# Round_Paws.net
KiCad netlist of a schematic drawn in EAGLE
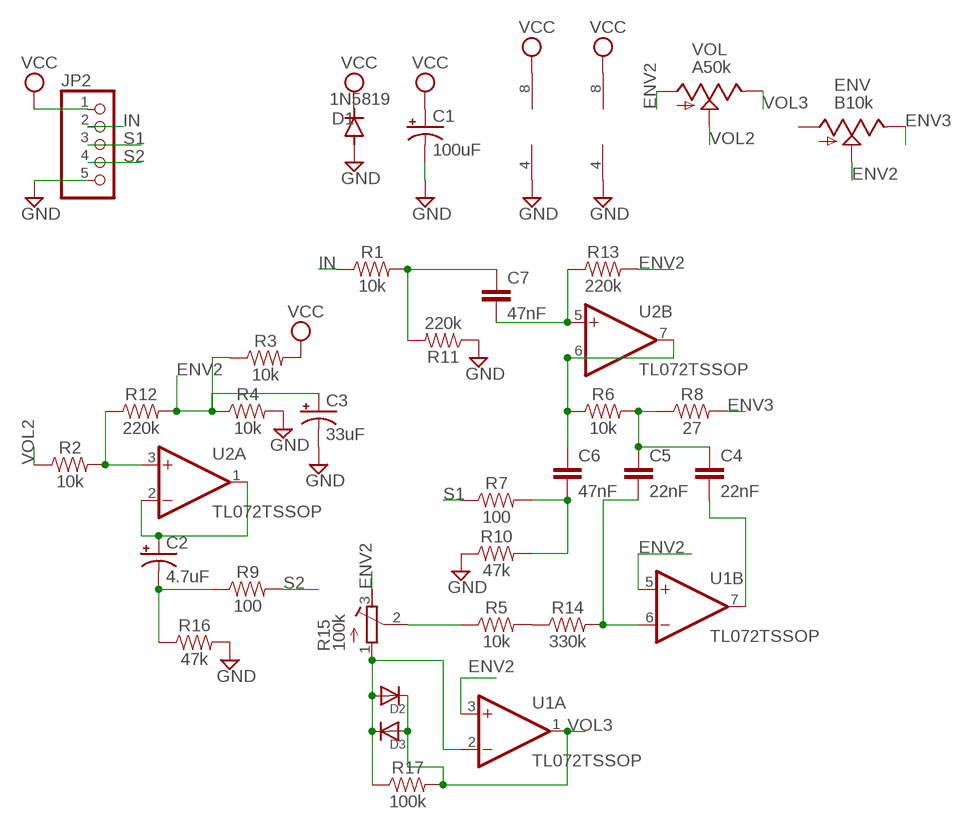
[diagram p0: schematic, sheet 1]

(export (version "E")
  (design (tool "Eeschema 10.0.6"))
  (components
    (comp (ref "C1")
      (value "100uF")
      (footprint "eagle-import:PAN_B_SMD+THRU")
      (libsource (lib "eagle-import") (part "CAP_SMD+THRUPAN_B"))
    )
    (comp (ref "C2")
      (value "4.7uF")
      (footprint "eagle-import:PAN_B_SMD+THRU")
      (libsource (lib "eagle-import") (part "CAP_SMD+THRUPAN_B"))
    )
    (comp (ref "C3")
      (value "33uF")
      (footprint "eagle-import:PAN_B_SMD+THRU")
      (libsource (lib "eagle-import") (part "CAP_SMD+THRUPAN_B"))
    )
    (comp (ref "C4")
      (value "22nF")
      (footprint "eagle-import:0603")
      (libsource (lib "eagle-import") (part "22NF/22,000PF-0603-50V-10%"))
    )
    (comp (ref "C5")
      (value "22nF")
      (footprint "eagle-import:0603")
      (libsource (lib "eagle-import") (part "22NF/22,000PF-0603-50V-10%"))
    )
    (comp (ref "C6")
      (value "47nF")
      (footprint "eagle-import:0603")
      (libsource (lib "eagle-import") (part "47NF-0603-25V-5%"))
    )
    (comp (ref "C7")
      (value "47nF")
      (footprint "eagle-import:0603")
      (libsource (lib "eagle-import") (part "47NF-0603-25V-5%"))
    )
    (comp (ref "D1")
      (value "1N5819")
      (footprint "eagle-import:SOD123")
      (libsource (lib "eagle-import") (part "DIODE-SOD123"))
    )
    (comp (ref "D2")
      (value "DIODESOD-123")
      (footprint "eagle-import:SOD-123")
      (libsource (lib "eagle-import") (part "DIODESOD-123"))
    )
    (comp (ref "D3")
      (value "DIODESOD-123")
      (footprint "eagle-import:SOD-123")
      (libsource (lib "eagle-import") (part "DIODESOD-123"))
    )
    (comp (ref "ENV")
      (value "B10k")
      (footprint "eagle-import:9MM_SNAP-IN_POT")
      (libsource (lib "eagle-import") (part "9MM_SNAP-IN_POT_"))
    )
    (comp (ref "JP2")
      (value "PINHD-1X5")
      (footprint "eagle-import:1X05")
      (libsource (lib "eagle-import") (part "PINHD-1X5"))
    )
    (comp (ref "R1")
      (value "10k")
      (footprint "eagle-import:0603")
      (libsource (lib "eagle-import") (part "10KOHM-0603-1/10W-1%"))
    )
    (comp (ref "R2")
      (value "10k")
      (footprint "eagle-import:0603")
      (libsource (lib "eagle-import") (part "10KOHM-0603-1/10W-1%"))
    )
    (comp (ref "R3")
      (value "10k")
      (footprint "eagle-import:0603")
      (libsource (lib "eagle-import") (part "10KOHM-0603-1/10W-1%"))
    )
    (comp (ref "R4")
      (value "10k")
      (footprint "eagle-import:0603")
      (libsource (lib "eagle-import") (part "10KOHM-0603-1/10W-1%"))
    )
    (comp (ref "R5")
      (value "10k")
      (footprint "eagle-import:0603")
      (libsource (lib "eagle-import") (part "10KOHM-0603-1/10W-1%"))
    )
    (comp (ref "R6")
      (value "10k")
      (footprint "eagle-import:0603")
      (libsource (lib "eagle-import") (part "10KOHM-0603-1/10W-1%"))
    )
    (comp (ref "R7")
      (value "100")
      (footprint "eagle-import:0603")
      (libsource (lib "eagle-import") (part "100OHM-0603-1/4W-5%"))
    )
    (comp (ref "R8")
      (value "27")
      (footprint "eagle-import:0603")
      (libsource (lib "eagle-import") (part "27OHM-0603-1/10W-1%"))
    )
    (comp (ref "R9")
      (value "100")
      (footprint "eagle-import:0603")
      (libsource (lib "eagle-import") (part "100OHM-0603-1/4W-5%"))
    )
    (comp (ref "R10")
      (value "47k")
      (footprint "eagle-import:0603")
      (libsource (lib "eagle-import") (part "47KOHM-0603-1/10W-1%"))
    )
    (comp (ref "R11")
      (value "220k")
      (footprint "eagle-import:0603")
      (libsource (lib "eagle-import") (part "220KOHM-0603-1/10W-1%"))
    )
    (comp (ref "R12")
      (value "220k")
      (footprint "eagle-import:0603")
      (libsource (lib "eagle-import") (part "220KOHM-0603-1/10W-1%"))
    )
    (comp (ref "R13")
      (value "220k")
      (footprint "eagle-import:0603")
      (libsource (lib "eagle-import") (part "220KOHM-0603-1/10W-1%"))
    )
    (comp (ref "R14")
      (value "330k")
      (footprint "eagle-import:0603")
      (libsource (lib "eagle-import") (part "330KOHM-0603-1/10W-1%"))
    )
    (comp (ref "R15")
      (value "100k")
      (footprint "eagle-import:RTRIM3296W")
      (libsource (lib "eagle-import") (part "R-TRIMM3296W"))
    )
    (comp (ref "R16")
      (value "47k")
      (footprint "eagle-import:0603")
      (libsource (lib "eagle-import") (part "47KOHM-0603-1/10W-1%"))
    )
    (comp (ref "R17")
      (value "100k")
      (footprint "eagle-import:0603")
      (libsource (lib "eagle-import") (part "100KOHM-0603-1/10W-1%"))
    )
    (comp (ref "U1")
      (value "TL072TSSOP")
      (footprint "eagle-import:TSSOP-8")
      (libsource (lib "eagle-import") (part "TL072TSSOP"))
    )
    (comp (ref "U2")
      (value "TL072TSSOP")
      (footprint "eagle-import:TSSOP-8")
      (libsource (lib "eagle-import") (part "TL072TSSOP"))
    )
    (comp (ref "VOL")
      (value "A50k")
      (footprint "eagle-import:9MM_SNAP-IN_POT")
      (libsource (lib "eagle-import") (part "9MM_SNAP-IN_POT_"))
    )
  )
  (nets
    (net (code "1") (name "/ENV2") (class "Default")
      (node (ref "C3") (pin "+") (pinfunction "+_+") (pintype "passive"))
      (node (ref "C3") (pin "++") (pinfunction "+_++") (pintype "passive"))
      (node (ref "ENV") (pin "2") (pinfunction "S_2") (pintype "passive"))
      (node (ref "R12") (pin "2") (pinfunction "2_2") (pintype "passive"))
      (node (ref "R13") (pin "2") (pinfunction "2_2") (pintype "passive"))
      (node (ref "R15") (pin "3") (pinfunction "E_3") (pintype "passive"))
      (node (ref "R3") (pin "1") (pinfunction "1_1") (pintype "passive"))
      (node (ref "R4") (pin "1") (pinfunction "1_1") (pintype "passive"))
      (node (ref "U1") (pin "3") (pinfunction "+IN_3") (pintype "input"))
      (node (ref "U1") (pin "5") (pinfunction "+IN_5") (pintype "input"))
      (node (ref "VOL") (pin "1") (pinfunction "A_1") (pintype "passive"))
    )
    (net (code "2") (name "/ENV3") (class "Default")
      (node (ref "ENV") (pin "3") (pinfunction "E_3") (pintype "passive"))
      (node (ref "R8") (pin "2") (pinfunction "2_2") (pintype "passive"))
    )
    (net (code "3") (name "/IN") (class "Default")
      (node (ref "JP2") (pin "2") (pinfunction "2_2") (pintype "passive"))
      (node (ref "R1") (pin "1") (pinfunction "1_1") (pintype "passive"))
    )
    (net (code "4") (name "/S1") (class "Default")
      (node (ref "JP2") (pin "3") (pinfunction "3_3") (pintype "passive"))
      (node (ref "R7") (pin "1") (pinfunction "1_1") (pintype "passive"))
    )
    (net (code "5") (name "/S2") (class "Default")
      (node (ref "JP2") (pin "4") (pinfunction "4_4") (pintype "passive"))
      (node (ref "R9") (pin "2") (pinfunction "2_2") (pintype "passive"))
    )
    (net (code "6") (name "/VOL2") (class "Default")
      (node (ref "R2") (pin "1") (pinfunction "1_1") (pintype "passive"))
      (node (ref "VOL") (pin "2") (pinfunction "S_2") (pintype "passive"))
    )
    (net (code "7") (name "/VOL3") (class "Default")
      (node (ref "D2") (pin "C") (pinfunction "C_C") (pintype "passive"))
      (node (ref "D3") (pin "A") (pinfunction "A_A") (pintype "passive"))
      (node (ref "R17") (pin "2") (pinfunction "2_2") (pintype "passive"))
      (node (ref "U1") (pin "1") (pinfunction "OUT_1") (pintype "output"))
      (node (ref "VOL") (pin "3") (pinfunction "E_3") (pintype "passive"))
    )
    (net (code "8") (name "GND") (class "Default")
      (node (ref "C1") (pin "-") (pinfunction "-_-") (pintype "passive"))
      (node (ref "C1") (pin "--") (pinfunction "-_--") (pintype "passive"))
      (node (ref "C3") (pin "-") (pinfunction "-_-") (pintype "passive"))
      (node (ref "C3") (pin "--") (pinfunction "-_--") (pintype "passive"))
      (node (ref "D1") (pin "A") (pinfunction "A_A") (pintype "passive"))
      (node (ref "JP2") (pin "5") (pinfunction "5_5") (pintype "passive"))
      (node (ref "R10") (pin "1") (pinfunction "1_1") (pintype "passive"))
      (node (ref "R11") (pin "1") (pinfunction "1_1") (pintype "passive"))
      (node (ref "R16") (pin "2") (pinfunction "2_2") (pintype "passive"))
      (node (ref "R4") (pin "2") (pinfunction "2_2") (pintype "passive"))
      (node (ref "U1") (pin "4") (pinfunction "V-_4") (pintype "power_in"))
      (node (ref "U2") (pin "4") (pinfunction "V-_4") (pintype "power_in"))
    )
    (net (code "9") (name "Net-(C2---Pad--)") (class "Default")
      (node (ref "C2") (pin "-") (pinfunction "-_-") (pintype "passive"))
      (node (ref "C2") (pin "--") (pinfunction "-_--") (pintype "passive"))
      (node (ref "R16") (pin "1") (pinfunction "1_1") (pintype "passive"))
      (node (ref "R9") (pin "1") (pinfunction "1_1") (pintype "passive"))
    )
    (net (code "10") (name "Net-(C4-Pad1)") (class "Default")
      (node (ref "C4") (pin "1") (pinfunction "1_1") (pintype "passive"))
      (node (ref "C5") (pin "1") (pinfunction "1_1") (pintype "passive"))
      (node (ref "R6") (pin "2") (pinfunction "2_2") (pintype "passive"))
      (node (ref "R8") (pin "1") (pinfunction "1_1") (pintype "passive"))
    )
    (net (code "11") (name "Net-(C6-Pad2)") (class "Default")
      (node (ref "C6") (pin "2") (pinfunction "2_2") (pintype "passive"))
      (node (ref "R10") (pin "2") (pinfunction "2_2") (pintype "passive"))
      (node (ref "R7") (pin "2") (pinfunction "2_2") (pintype "passive"))
    )
    (net (code "12") (name "Net-(C7-Pad1)") (class "Default")
      (node (ref "C7") (pin "1") (pinfunction "1_1") (pintype "passive"))
      (node (ref "R1") (pin "2") (pinfunction "2_2") (pintype "passive"))
      (node (ref "R11") (pin "2") (pinfunction "2_2") (pintype "passive"))
    )
    (net (code "13") (name "Net-(R14-Pad1)") (class "Default")
      (node (ref "R14") (pin "1") (pinfunction "1_1") (pintype "passive"))
      (node (ref "R5") (pin "2") (pinfunction "2_2") (pintype "passive"))
    )
    (net (code "14") (name "Net-(R15-A)") (class "Default")
      (node (ref "D2") (pin "A") (pinfunction "A_A") (pintype "passive"))
      (node (ref "D3") (pin "C") (pinfunction "C_C") (pintype "passive"))
      (node (ref "R15") (pin "1") (pinfunction "A_1") (pintype "passive"))
      (node (ref "R17") (pin "1") (pinfunction "1_1") (pintype "passive"))
      (node (ref "U1") (pin "2") (pinfunction "-IN_2") (pintype "input"))
    )
    (net (code "15") (name "Net-(R15-S)") (class "Default")
      (node (ref "R15") (pin "2") (pinfunction "S_2") (pintype "passive"))
      (node (ref "R5") (pin "1") (pinfunction "1_1") (pintype "passive"))
    )
    (net (code "16") (name "Net-(U1B--IN)") (class "Default")
      (node (ref "C5") (pin "2") (pinfunction "2_2") (pintype "passive"))
      (node (ref "R14") (pin "2") (pinfunction "2_2") (pintype "passive"))
      (node (ref "U1") (pin "6") (pinfunction "-IN_6") (pintype "input"))
    )
    (net (code "17") (name "Net-(U1B-OUT)") (class "Default")
      (node (ref "C4") (pin "2") (pinfunction "2_2") (pintype "passive"))
      (node (ref "U1") (pin "7") (pinfunction "OUT_7") (pintype "output"))
    )
    (net (code "18") (name "Net-(U2A-+IN)") (class "Default")
      (node (ref "R12") (pin "1") (pinfunction "1_1") (pintype "passive"))
      (node (ref "R2") (pin "2") (pinfunction "2_2") (pintype "passive"))
      (node (ref "U2") (pin "3") (pinfunction "+IN_3") (pintype "input"))
    )
    (net (code "19") (name "Net-(U2A--IN)") (class "Default")
      (node (ref "C2") (pin "+") (pinfunction "+_+") (pintype "passive"))
      (node (ref "C2") (pin "++") (pinfunction "+_++") (pintype "passive"))
      (node (ref "U2") (pin "1") (pinfunction "OUT_1") (pintype "output"))
      (node (ref "U2") (pin "2") (pinfunction "-IN_2") (pintype "input"))
    )
    (net (code "20") (name "Net-(U2B-+IN)") (class "Default")
      (node (ref "C7") (pin "2") (pinfunction "2_2") (pintype "passive"))
      (node (ref "R13") (pin "1") (pinfunction "1_1") (pintype "passive"))
      (node (ref "U2") (pin "5") (pinfunction "+IN_5") (pintype "input"))
    )
    (net (code "21") (name "Net-(U2B--IN)") (class "Default")
      (node (ref "C6") (pin "1") (pinfunction "1_1") (pintype "passive"))
      (node (ref "R6") (pin "1") (pinfunction "1_1") (pintype "passive"))
      (node (ref "U2") (pin "6") (pinfunction "-IN_6") (pintype "input"))
      (node (ref "U2") (pin "7") (pinfunction "OUT_7") (pintype "output"))
    )
    (net (code "22") (name "VCC") (class "Default")
      (node (ref "C1") (pin "+") (pinfunction "+_+") (pintype "passive"))
      (node (ref "C1") (pin "++") (pinfunction "+_++") (pintype "passive"))
      (node (ref "D1") (pin "C") (pinfunction "C_C") (pintype "passive"))
      (node (ref "JP2") (pin "1") (pinfunction "1_1") (pintype "passive"))
      (node (ref "R3") (pin "2") (pinfunction "2_2") (pintype "passive"))
      (node (ref "U1") (pin "8") (pinfunction "V+_8") (pintype "power_in"))
      (node (ref "U2") (pin "8") (pinfunction "V+_8") (pintype "power_in"))
    )
    (net (code "23") (name "unconnected-(ENV-A-Pad1)") (class "Default")
      (node (ref "ENV") (pin "1") (pinfunction "A_1") (pintype "passive"))
    )
  )
)
